# ST-LINK.net
KiCad netlist of a schematic drawn in Altium Designer
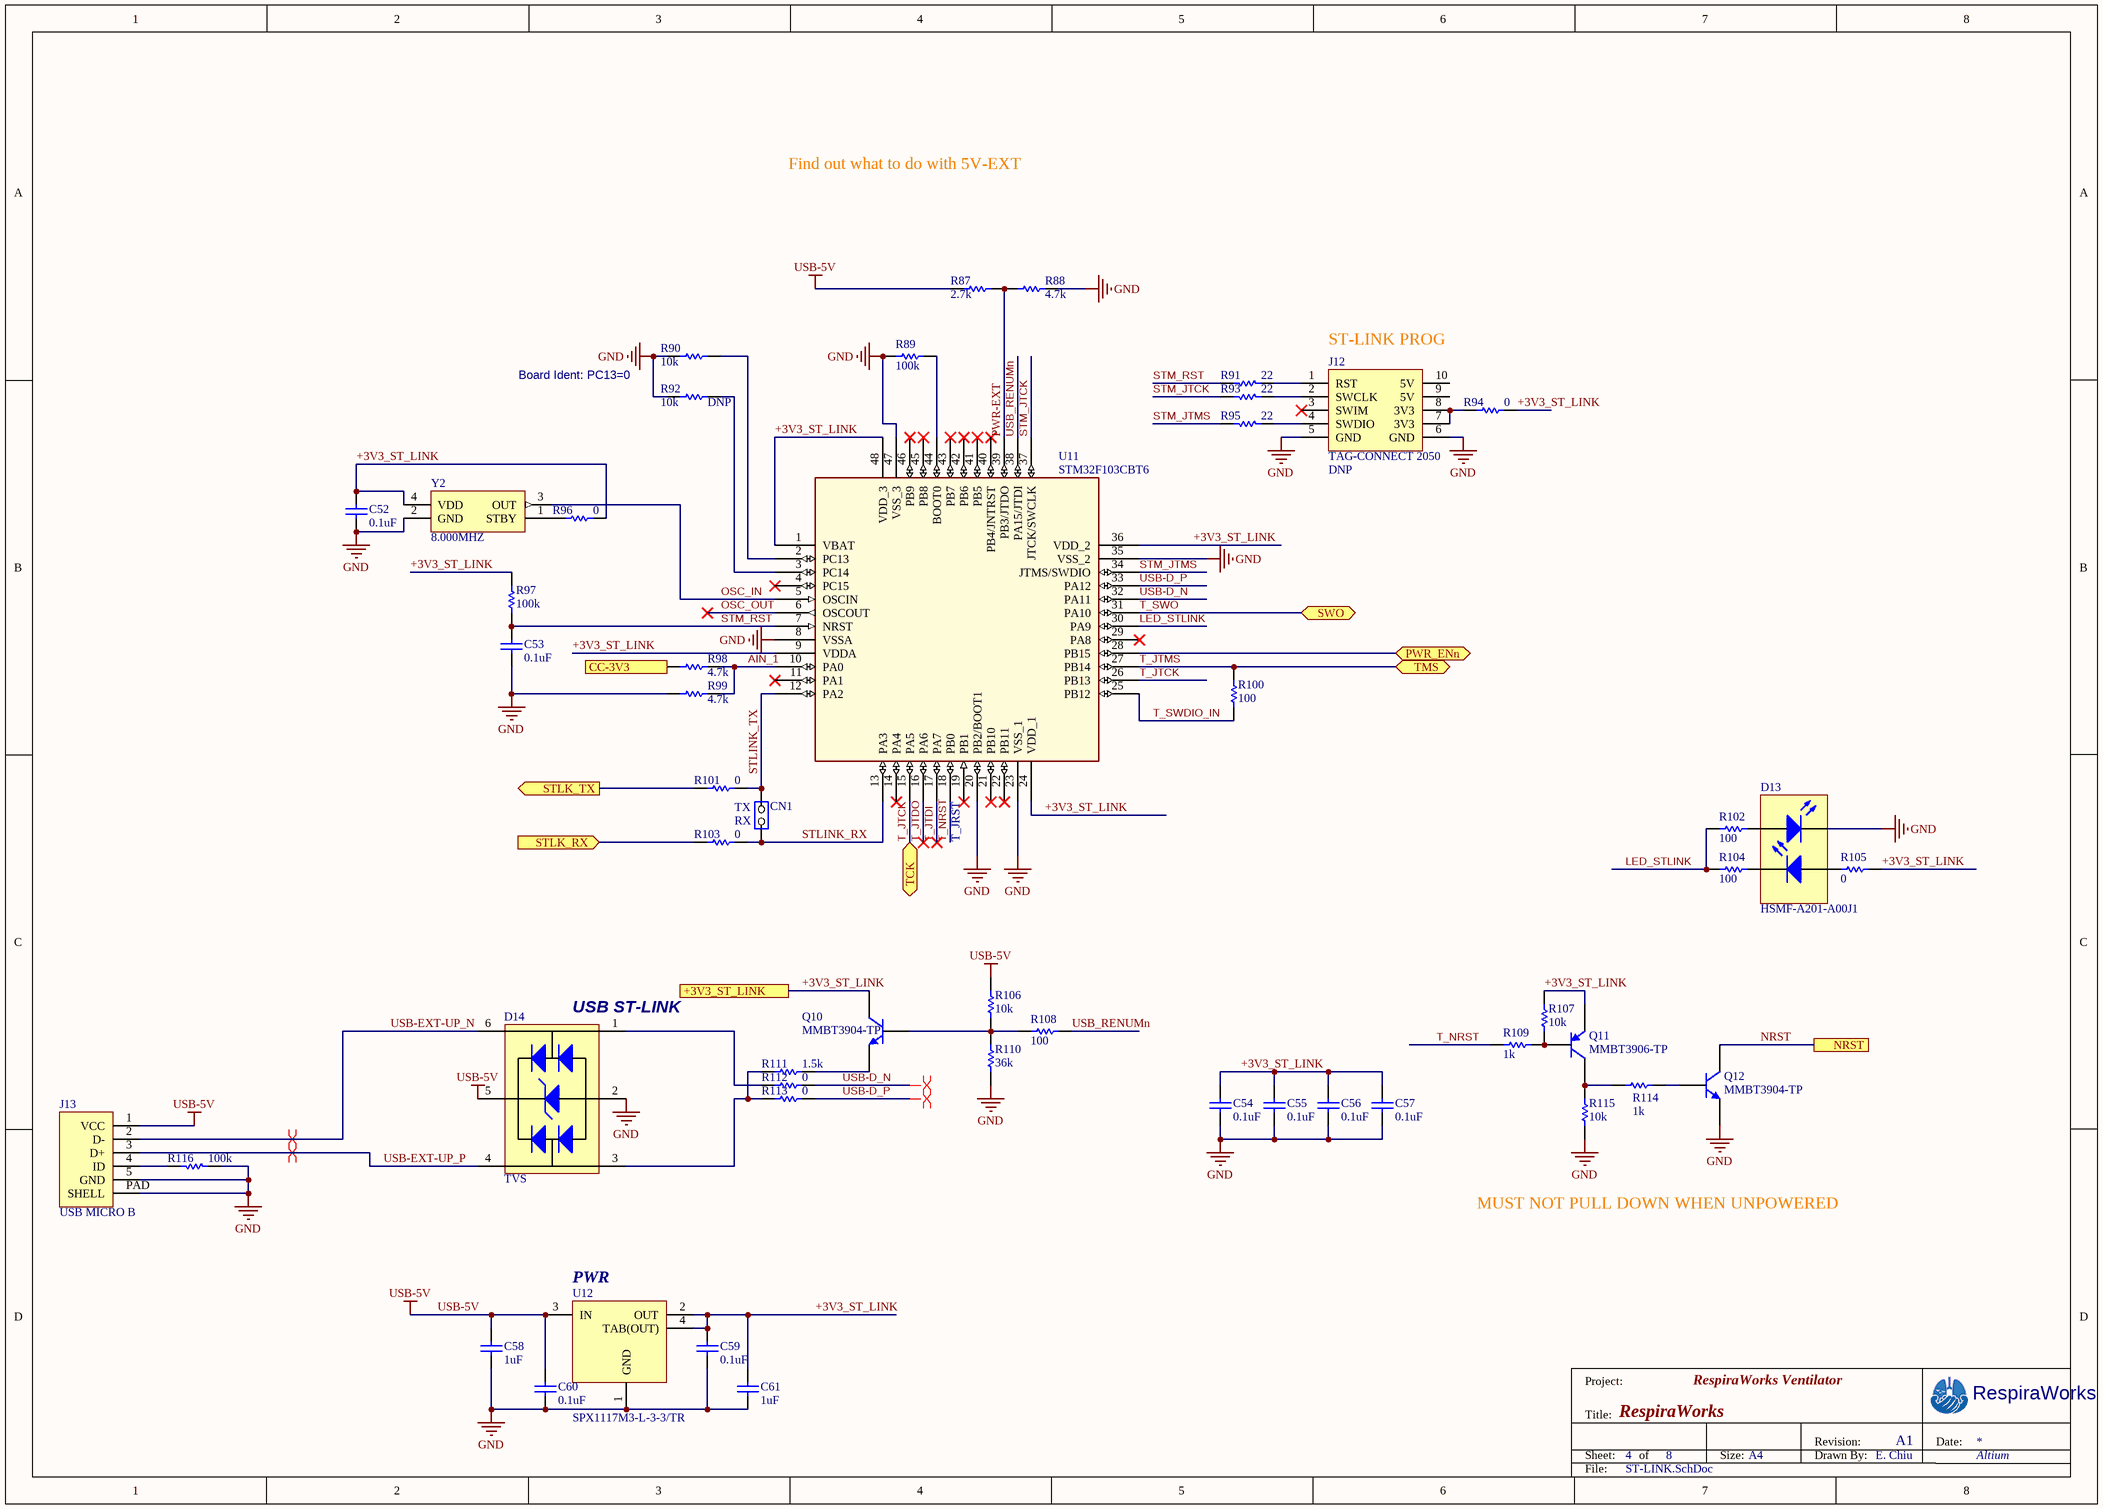
[diagram p0: ST-LINK.SchDoc]

(export (version "E")
  (design (tool "Eeschema 10.0.6"))
  (components
    (comp (ref "C52")
      (value "0.1uF")
      (footprint "CAP0603")
      (description "Cap 0603")
      (fields (field (name "MANUFACTURER") "Yageo") (field (name "VOLTAGE") "25V"))
      (libsource (lib "generic") (part "CAP 0603"))
    )
    (comp (ref "C53")
      (value "0.1uF")
      (footprint "CAP0603")
      (description "Cap 0603")
      (fields (field (name "MANUFACTURER") "Yageo") (field (name "VOLTAGE") "25V"))
      (libsource (lib "generic") (part "CAP 0603"))
    )
    (comp (ref "C54")
      (value "0.1uF")
      (footprint "CAP0603")
      (description "Cap 0603")
      (fields (field (name "MANUFACTURER") "Yageo") (field (name "VOLTAGE") "25V"))
      (libsource (lib "generic") (part "CAP 0603"))
    )
    (comp (ref "C55")
      (value "0.1uF")
      (footprint "CAP0603")
      (description "Cap 0603")
      (fields (field (name "MANUFACTURER") "Yageo") (field (name "VOLTAGE") "25V"))
      (libsource (lib "generic") (part "CAP 0603"))
    )
    (comp (ref "C56")
      (value "0.1uF")
      (footprint "CAP0603")
      (description "Cap 0603")
      (fields (field (name "MANUFACTURER") "Yageo") (field (name "VOLTAGE") "25V"))
      (libsource (lib "generic") (part "CAP 0603"))
    )
    (comp (ref "C57")
      (value "0.1uF")
      (footprint "CAP0603")
      (description "Cap 0603")
      (fields (field (name "MANUFACTURER") "Yageo") (field (name "VOLTAGE") "25V"))
      (libsource (lib "generic") (part "CAP 0603"))
    )
    (comp (ref "C58")
      (value "1uF")
      (footprint "CAP0603")
      (description "Cap 0603")
      (fields (field (name "MANUFACTURER") "TDK") (field (name "VOLTAGE") "25V"))
      (libsource (lib "generic") (part "CAP 0603"))
    )
    (comp (ref "C59")
      (value "0.1uF")
      (footprint "CAP0603")
      (description "Cap 0603")
      (fields (field (name "MANUFACTURER") "Yageo") (field (name "VOLTAGE") "25V"))
      (libsource (lib "generic") (part "CAP 0603"))
    )
    (comp (ref "C60")
      (value "0.1uF")
      (footprint "CAP0603")
      (description "Cap 0603")
      (fields (field (name "MANUFACTURER") "Yageo") (field (name "VOLTAGE") "25V"))
      (libsource (lib "generic") (part "CAP 0603"))
    )
    (comp (ref "C61")
      (value "1uF")
      (footprint "CAP0603")
      (description "Cap 0603")
      (fields (field (name "MANUFACTURER") "TDK") (field (name "VOLTAGE") "25V"))
      (libsource (lib "generic") (part "CAP 0603"))
    )
    (comp (ref "CN1")
      (value "~")
      (footprint "HDR1X2")
      (description "HEADER 2")
      (fields (field (name "MANUFACTURER") "Wurth"))
      (libsource (lib "MCD_TOOLS") (part "JP2"))
    )
    (comp (ref "D13")
      (value "*")
      (footprint "4-LED3228")
      (description "LED 3528 4PIN")
      (fields (field (name "MANUFACTURER P/N") "HSMF-A201-A00J1") (field (name "MANUFACTURER") "Broadcom"))
      (libsource (lib "generic") (part "LED 3228 4PIN"))
    )
    (comp (ref "D14")
      (value "TVS")
      (footprint "6-SOT23")
      (description "TVS, USB2.0, 15kV")
      (fields (field (name "MANUFACTURER") "ST Micro"))
      (libsource (lib "st") (part "USBLC6-2SC6"))
    )
    (comp (ref "J12")
      (value "TAG-CONNECT 2050")
      (footprint "TAG-CONNECT-2050")
      (description "10-pin TAG-CONNECT Bed of Nails footprint")
      (fields (field (name "DO NOT POPULATE") "DNP"))
      (libsource (lib "special") (part "TC-2050-STLINK"))
    )
    (comp (ref "J13")
      (value "USB MICRO B")
      (footprint "10118192-0001LF")
      (description "SMT USB MICRO B RECEPTACLE")
      (fields (field (name "MANUFACTURER") "Amphenol"))
      (libsource (lib "amphenol") (part "10118192-0001LF"))
    )
    (comp (ref "Q10")
      (value "MMBT3904")
      (footprint "3-SOT23")
      (description "Transistor, BJT NPN, General Purpose 40V")
      (fields
        (field (name "MANUFACTURER") "Micro Commercial")
        (field (name "MANUFACTURER P/N") "MMBT3904-TP")
      )
      (libsource (lib "fairchild") (part "MMBT3904"))
    )
    (comp (ref "Q11")
      (value "MMBT3906")
      (footprint "3-SOT23")
      (description "Transistor, BJT PNP, General Purpose 40V")
      (fields
        (field (name "MANUFACTURER") "Micro Commercial")
        (field (name "MANUFACTURER P/N") "MMBT3906-TP")
      )
      (libsource (lib "fairchild") (part "MMBT3906"))
    )
    (comp (ref "Q12")
      (value "MMBT3904")
      (footprint "3-SOT23")
      (description "Transistor, BJT NPN, General Purpose 40V")
      (fields
        (field (name "MANUFACTURER") "Micro Commercial")
        (field (name "MANUFACTURER P/N") "MMBT3904-TP")
      )
      (libsource (lib "fairchild") (part "MMBT3904"))
    )
    (comp (ref "R87")
      (value "2.7k")
      (footprint "RES0603")
      (description "Res 0603")
      (fields (field (name "MANUFACTURER") "Panasonic") (field (name "TOLERANCE") "1%"))
      (libsource (lib "generic") (part "RES 0603"))
    )
    (comp (ref "R88")
      (value "4.7k")
      (footprint "RES0603")
      (description "Res 0603")
      (fields (field (name "MANUFACTURER") "Yageo") (field (name "TOLERANCE") "1%"))
      (libsource (lib "generic") (part "RES 0603"))
    )
    (comp (ref "R89")
      (value "100k")
      (footprint "RES0603")
      (description "Res 0603")
      (fields (field (name "MANUFACTURER") "Panasonic") (field (name "TOLERANCE") "1%"))
      (libsource (lib "generic") (part "RES 0603"))
    )
    (comp (ref "R90")
      (value "10k")
      (footprint "RES0603")
      (description "Res 0603")
      (fields (field (name "MANUFACTURER") "Panasonic") (field (name "Comment") "RES 0603"))
      (libsource (lib "generic") (part "RES 0603"))
    )
    (comp (ref "R91")
      (value "22")
      (footprint "RES0603")
      (description "Res 0603")
      (fields (field (name "MANUFACTURER") "Yageo") (field (name "TOLERANCE") "1%"))
      (libsource (lib "generic") (part "RES 0603"))
    )
    (comp (ref "R92")
      (value "10k")
      (footprint "RES0603")
      (description "Res 0603")
      (fields
        (field (name "MANUFACTURER") "Panasonic")
        (field (name "DO NOT POPULATE") "DNP")
        (field (name "Comment") "RES 0603")
      )
      (libsource (lib "generic") (part "RES 0603"))
    )
    (comp (ref "R93")
      (value "22")
      (footprint "RES0603")
      (description "Res 0603")
      (fields (field (name "MANUFACTURER") "Yageo") (field (name "TOLERANCE") "1%"))
      (libsource (lib "generic") (part "RES 0603"))
    )
    (comp (ref "R94")
      (value "0")
      (footprint "RES0603")
      (description "Res 0603")
      (fields (field (name "MANUFACTURER") "Panasonic") (field (name "Comment") "RES 0603"))
      (libsource (lib "generic") (part "RES 0603"))
    )
    (comp (ref "R95")
      (value "22")
      (footprint "RES0603")
      (description "Res 0603")
      (fields (field (name "MANUFACTURER") "Yageo") (field (name "TOLERANCE") "1%"))
      (libsource (lib "generic") (part "RES 0603"))
    )
    (comp (ref "R96")
      (value "0")
      (footprint "RES0603")
      (description "Res 0603")
      (fields (field (name "MANUFACTURER") "Panasonic") (field (name "Comment") "RES 0603"))
      (libsource (lib "generic") (part "RES 0603"))
    )
    (comp (ref "R97")
      (value "100k")
      (footprint "RES0603")
      (description "Res 0603")
      (fields (field (name "MANUFACTURER") "Panasonic") (field (name "TOLERANCE") "1%"))
      (libsource (lib "generic") (part "RES 0603"))
    )
    (comp (ref "R98")
      (value "4.7k")
      (footprint "RES0603")
      (description "Res 0603")
      (fields (field (name "MANUFACTURER") "Yageo") (field (name "TOLERANCE") "1%"))
      (libsource (lib "generic") (part "RES 0603"))
    )
    (comp (ref "R99")
      (value "4.7k")
      (footprint "RES0603")
      (description "Res 0603")
      (fields (field (name "MANUFACTURER") "Yageo") (field (name "TOLERANCE") "1%"))
      (libsource (lib "generic") (part "RES 0603"))
    )
    (comp (ref "R100")
      (value "100")
      (footprint "RES0603")
      (description "Res 0603")
      (fields (field (name "MANUFACTURER") "Yageo") (field (name "TOLERANCE") "1%"))
      (libsource (lib "generic") (part "RES 0603"))
    )
    (comp (ref "R101")
      (value "0")
      (footprint "RES0603")
      (description "Res 0603")
      (fields (field (name "MANUFACTURER") "Panasonic") (field (name "Comment") "RES 0603"))
      (libsource (lib "generic") (part "RES 0603"))
    )
    (comp (ref "R102")
      (value "100")
      (footprint "RES0603")
      (description "Res 0603")
      (fields (field (name "MANUFACTURER") "Yageo") (field (name "TOLERANCE") "1%"))
      (libsource (lib "generic") (part "RES 0603"))
    )
    (comp (ref "R103")
      (value "0")
      (footprint "RES0603")
      (description "Res 0603")
      (fields (field (name "MANUFACTURER") "Panasonic") (field (name "Comment") "RES 0603"))
      (libsource (lib "generic") (part "RES 0603"))
    )
    (comp (ref "R104")
      (value "100")
      (footprint "RES0603")
      (description "Res 0603")
      (fields (field (name "MANUFACTURER") "Yageo") (field (name "TOLERANCE") "1%"))
      (libsource (lib "generic") (part "RES 0603"))
    )
    (comp (ref "R105")
      (value "0")
      (footprint "RES0603")
      (description "Res 0603")
      (fields (field (name "MANUFACTURER") "Panasonic") (field (name "Comment") "RES 0603"))
      (libsource (lib "generic") (part "RES 0603"))
    )
    (comp (ref "R106")
      (value "10k")
      (footprint "RES0603")
      (description "Res 0603")
      (fields (field (name "MANUFACTURER") "Panasonic") (field (name "Comment") "RES 0603"))
      (libsource (lib "generic") (part "RES 0603"))
    )
    (comp (ref "R107")
      (value "10k")
      (footprint "RES0603")
      (description "Res 0603")
      (fields (field (name "MANUFACTURER") "Panasonic") (field (name "Comment") "RES 0603"))
      (libsource (lib "generic") (part "RES 0603"))
    )
    (comp (ref "R108")
      (value "100")
      (footprint "RES0603")
      (description "Res 0603")
      (fields (field (name "MANUFACTURER") "Yageo") (field (name "TOLERANCE") "1%"))
      (libsource (lib "generic") (part "RES 0603"))
    )
    (comp (ref "R109")
      (value "1k")
      (footprint "RES0603")
      (description "Res 0603")
      (fields (field (name "MANUFACTURER") "Yageo") (field (name "TOLERANCE") "1%"))
      (libsource (lib "generic") (part "RES 0603"))
    )
    (comp (ref "R110")
      (value "36k")
      (footprint "RES0603")
      (description "Res 0603")
      (fields (field (name "MANUFACTURER") "Yageo") (field (name "TOLERANCE") "1%"))
      (libsource (lib "generic") (part "RES 0603"))
    )
    (comp (ref "R111")
      (value "1.5k")
      (footprint "RES0603")
      (description "Res 0603")
      (fields (field (name "MANUFACTURER") "Yageo") (field (name "TOLERANCE") "1%"))
      (libsource (lib "generic") (part "RES 0603"))
    )
    (comp (ref "R112")
      (value "0")
      (footprint "RES0603")
      (description "Res 0603")
      (fields (field (name "MANUFACTURER") "Panasonic") (field (name "Comment") "RES 0603"))
      (libsource (lib "generic") (part "RES 0603"))
    )
    (comp (ref "R113")
      (value "0")
      (footprint "RES0603")
      (description "Res 0603")
      (fields (field (name "MANUFACTURER") "Panasonic") (field (name "Comment") "RES 0603"))
      (libsource (lib "generic") (part "RES 0603"))
    )
    (comp (ref "R114")
      (value "1k")
      (footprint "RES0603")
      (description "Res 0603")
      (fields (field (name "MANUFACTURER") "Yageo") (field (name "TOLERANCE") "1%"))
      (libsource (lib "generic") (part "RES 0603"))
    )
    (comp (ref "R115")
      (value "10k")
      (footprint "RES0603")
      (description "Res 0603")
      (fields (field (name "MANUFACTURER") "Panasonic") (field (name "Comment") "RES 0603"))
      (libsource (lib "generic") (part "RES 0603"))
    )
    (comp (ref "R116")
      (value "100k")
      (footprint "RES0603")
      (description "Res 0603")
      (fields (field (name "MANUFACTURER") "Panasonic") (field (name "TOLERANCE") "1%"))
      (libsource (lib "generic") (part "RES 0603"))
    )
    (comp (ref "U11")
      (value "STM32F103CBT6")
      (footprint "48-LQFP")
      (description "Medium-density performance line ARM-based 32-bit MCU with 64KB Flash")
      (fields (field (name "MANUFACTURER") "ST Micro"))
      (libsource (lib "Nucleo_64") (part "STM32F103CBT6"))
    )
    (comp (ref "U12")
      (value "NCP1117ST33T3G")
      (footprint "3-SOT223")
      (description "LDO, 3.3V out, 1A, 20V in, SOT-223, 0.8W Pd max")
      (fields (field (name "MANUFACTURER") "Exar") (field (name "MANUFACTURER P/N") "SPX1117M3-L-3-3/TR"))
      (libsource (lib "on-semi") (part "NCP1117ST33T3G"))
    )
    (comp (ref "Y2")
      (value "8.000MHZ")
      (footprint "4-OSC3225")
      (description "OSC MEMS 8.000MHZ CMOS SMD")
      (fields (field (name "MANUFACTURER") "Abracon") (field (name "TOLERANCE") "50ppm"))
      (libsource (lib "abracon") (part "ASEMB-8.000MHZ-LC-T"))
    )
  )
  (nets
    (net (code "1") (name "/+3V3_ST_LINK") (class "Default")
      (node (ref "C52") (pin "2") (pinfunction "2_2") (pintype "passive"))
      (node (ref "C54") (pin "2") (pinfunction "2_2") (pintype "passive"))
      (node (ref "C55") (pin "2") (pinfunction "2_2") (pintype "passive"))
      (node (ref "C56") (pin "2") (pinfunction "2_2") (pintype "passive"))
      (node (ref "C57") (pin "2") (pinfunction "2_2") (pintype "passive"))
      (node (ref "C59") (pin "2") (pinfunction "2_2") (pintype "passive"))
      (node (ref "C61") (pin "2") (pinfunction "2_2") (pintype "passive"))
      (node (ref "Q10") (pin "3") (pinfunction "C_3") (pintype "passive"))
      (node (ref "Q11") (pin "2") (pinfunction "E_2") (pintype "passive"))
      (node (ref "R105") (pin "2") (pinfunction "2_2") (pintype "passive"))
      (node (ref "R107") (pin "1") (pinfunction "1_1") (pintype "passive"))
      (node (ref "R94") (pin "2") (pinfunction "2_2") (pintype "passive"))
      (node (ref "R96") (pin "1") (pinfunction "1_1") (pintype "passive"))
      (node (ref "R97") (pin "2") (pinfunction "2_2") (pintype "passive"))
      (node (ref "U11") (pin "1") (pinfunction "VBAT_1") (pintype "power_in"))
      (node (ref "U11") (pin "24") (pinfunction "VDD_1_24") (pintype "power_in"))
      (node (ref "U11") (pin "36") (pinfunction "VDD_2_36") (pintype "power_in"))
      (node (ref "U11") (pin "48") (pinfunction "VDD_3_48") (pintype "power_in"))
      (node (ref "U11") (pin "9") (pinfunction "VDDA_9") (pintype "power_in"))
      (node (ref "U12") (pin "2") (pinfunction "OUT_2") (pintype "passive"))
      (node (ref "U12") (pin "4") (pinfunction "TAB(OUT)_4") (pintype "passive"))
      (node (ref "Y2") (pin "4") (pinfunction "VDD_4") (pintype "passive"))
    )
    (net (code "2") (name "/AIN_1") (class "Default")
      (node (ref "R98") (pin "2") (pinfunction "2_2") (pintype "passive"))
      (node (ref "R99") (pin "2") (pinfunction "2_2") (pintype "passive"))
      (node (ref "U11") (pin "10") (pinfunction "PA0_10") (pintype "bidirectional"))
    )
    (net (code "3") (name "/CC-3V3") (class "Default")
      (node (ref "R98") (pin "1") (pinfunction "1_1") (pintype "passive"))
    )
    (net (code "4") (name "/LED_STLINK") (class "Default")
      (node (ref "R102") (pin "1") (pinfunction "1_1") (pintype "passive"))
      (node (ref "R104") (pin "1") (pinfunction "1_1") (pintype "passive"))
      (node (ref "U11") (pin "30") (pinfunction "PA9_30") (pintype "bidirectional"))
    )
    (net (code "5") (name "/NRST") (class "Default")
      (node (ref "Q12") (pin "3") (pinfunction "C_3") (pintype "passive"))
    )
    (net (code "6") (name "/OSC_IN") (class "Default")
      (node (ref "U11") (pin "5") (pinfunction "OSCIN_5") (pintype "input"))
      (node (ref "Y2") (pin "3") (pinfunction "OUT_3") (pintype "output"))
    )
    (net (code "7") (name "/OSC_OUT") (class "Default")
      (node (ref "U11") (pin "6") (pinfunction "OSCOUT_6") (pintype "output+no_connect"))
    )
    (net (code "8") (name "/PWR-EXT") (class "Default")
      (node (ref "R87") (pin "2") (pinfunction "2_2") (pintype "passive"))
      (node (ref "R88") (pin "1") (pinfunction "1_1") (pintype "passive"))
      (node (ref "U11") (pin "39") (pinfunction "PB3/JTDO_39") (pintype "bidirectional"))
    )
    (net (code "9") (name "/PWR_ENn") (class "Default")
      (node (ref "U11") (pin "28") (pinfunction "PB15_28") (pintype "bidirectional"))
    )
    (net (code "10") (name "/STLINK_RX") (class "Default")
      (node (ref "CN1") (pin "1") (pinfunction "COMMON_1") (pintype "passive"))
      (node (ref "R103") (pin "2") (pinfunction "2_2") (pintype "passive"))
      (node (ref "U11") (pin "13") (pinfunction "PA3_13") (pintype "bidirectional"))
    )
    (net (code "11") (name "/STLINK_TX") (class "Default")
      (node (ref "CN1") (pin "2") (pinfunction "NO_2") (pintype "passive"))
      (node (ref "R101") (pin "2") (pinfunction "2_2") (pintype "passive"))
      (node (ref "U11") (pin "12") (pinfunction "PA2_12") (pintype "bidirectional"))
    )
    (net (code "12") (name "/STLK_RX") (class "Default")
      (node (ref "R103") (pin "1") (pinfunction "1_1") (pintype "passive"))
    )
    (net (code "13") (name "/STLK_TX") (class "Default")
      (node (ref "R101") (pin "1") (pinfunction "1_1") (pintype "passive"))
    )
    (net (code "14") (name "/STM_JTCK") (class "Default")
      (node (ref "R93") (pin "2") (pinfunction "2_2") (pintype "passive"))
      (node (ref "U11") (pin "37") (pinfunction "JTCK/SWCLK_37") (pintype "bidirectional"))
    )
    (net (code "15") (name "/STM_JTMS") (class "Default")
      (node (ref "R95") (pin "2") (pinfunction "2_2") (pintype "passive"))
      (node (ref "U11") (pin "34") (pinfunction "JTMS/SWDIO_34") (pintype "bidirectional"))
    )
    (net (code "16") (name "/STM_RST") (class "Default")
      (node (ref "C53") (pin "2") (pinfunction "2_2") (pintype "passive"))
      (node (ref "R91") (pin "2") (pinfunction "2_2") (pintype "passive"))
      (node (ref "R97") (pin "1") (pinfunction "1_1") (pintype "passive"))
      (node (ref "U11") (pin "7") (pinfunction "NRST_7") (pintype "input"))
    )
    (net (code "17") (name "/T_JTCK") (class "Default")
      (node (ref "U11") (pin "15") (pinfunction "PA5_15") (pintype "bidirectional"))
      (node (ref "U11") (pin "26") (pinfunction "PB13_26") (pintype "bidirectional"))
    )
    (net (code "18") (name "/T_JTDI") (class "Default")
      (node (ref "U11") (pin "17") (pinfunction "PA7_17") (pintype "bidirectional+no_connect"))
    )
    (net (code "19") (name "/T_JTDO") (class "Default")
      (node (ref "U11") (pin "16") (pinfunction "PA6_16") (pintype "bidirectional+no_connect"))
    )
    (net (code "20") (name "/T_JTMS") (class "Default")
      (node (ref "R100") (pin "2") (pinfunction "2_2") (pintype "passive"))
      (node (ref "U11") (pin "27") (pinfunction "PB14_27") (pintype "bidirectional"))
    )
    (net (code "21") (name "/T_NRST") (class "Default")
      (node (ref "R109") (pin "2") (pinfunction "2_2") (pintype "passive"))
      (node (ref "U11") (pin "18") (pinfunction "PB0_18") (pintype "bidirectional"))
    )
    (net (code "22") (name "/T_SWDIO_IN") (class "Default")
      (node (ref "R100") (pin "1") (pinfunction "1_1") (pintype "passive"))
      (node (ref "U11") (pin "25") (pinfunction "PB12_25") (pintype "bidirectional"))
    )
    (net (code "23") (name "/T_SWO") (class "Default")
      (node (ref "U11") (pin "31") (pinfunction "PA10_31") (pintype "bidirectional"))
    )
    (net (code "24") (name "/USB-D_N") (class "Default")
      (node (ref "R112") (pin "2") (pinfunction "2_2") (pintype "passive"))
      (node (ref "U11") (pin "32") (pinfunction "PA11_32") (pintype "bidirectional"))
    )
    (net (code "25") (name "/USB-D_P") (class "Default")
      (node (ref "R113") (pin "2") (pinfunction "2_2") (pintype "passive"))
      (node (ref "U11") (pin "33") (pinfunction "PA12_33") (pintype "bidirectional"))
    )
    (net (code "26") (name "/USB-EXT-UP_N") (class "Default")
      (node (ref "D14") (pin "6") (pinfunction "IO1_6") (pintype "passive"))
      (node (ref "J13") (pin "2") (pinfunction "D-_2") (pintype "passive"))
    )
    (net (code "27") (name "/USB-EXT-UP_P") (class "Default")
      (node (ref "D14") (pin "4") (pinfunction "IO3_4") (pintype "passive"))
      (node (ref "J13") (pin "3") (pinfunction "D+_3") (pintype "passive"))
    )
    (net (code "28") (name "/USB_RENUMn") (class "Default")
      (node (ref "R108") (pin "1") (pinfunction "1_1") (pintype "passive"))
      (node (ref "U11") (pin "38") (pinfunction "PA15/JTDI_38") (pintype "bidirectional"))
    )
    (net (code "29") (name "GND") (class "Default")
      (node (ref "C52") (pin "1") (pinfunction "1_1") (pintype "passive"))
      (node (ref "C53") (pin "1") (pinfunction "1_1") (pintype "passive"))
      (node (ref "C54") (pin "1") (pinfunction "1_1") (pintype "passive"))
      (node (ref "C55") (pin "1") (pinfunction "1_1") (pintype "passive"))
      (node (ref "C56") (pin "1") (pinfunction "1_1") (pintype "passive"))
      (node (ref "C57") (pin "1") (pinfunction "1_1") (pintype "passive"))
      (node (ref "C58") (pin "1") (pinfunction "1_1") (pintype "passive"))
      (node (ref "C59") (pin "1") (pinfunction "1_1") (pintype "passive"))
      (node (ref "C60") (pin "1") (pinfunction "1_1") (pintype "passive"))
      (node (ref "C61") (pin "1") (pinfunction "1_1") (pintype "passive"))
      (node (ref "D13") (pin "1") (pinfunction "K1_1") (pintype "passive"))
      (node (ref "D14") (pin "2") (pinfunction "GND_2") (pintype "passive"))
      (node (ref "J12") (pin "5") (pinfunction "GND_5") (pintype "passive"))
      (node (ref "J12") (pin "6") (pinfunction "GND_6") (pintype "passive"))
      (node (ref "J13") (pin "5") (pinfunction "GND_5") (pintype "passive"))
      (node (ref "J13") (pin "PAD") (pinfunction "SHELL_PAD") (pintype "passive"))
      (node (ref "Q12") (pin "2") (pinfunction "E_2") (pintype "passive"))
      (node (ref "R110") (pin "1") (pinfunction "1_1") (pintype "passive"))
      (node (ref "R115") (pin "2") (pinfunction "2_2") (pintype "passive"))
      (node (ref "R116") (pin "1") (pinfunction "1_1") (pintype "passive"))
      (node (ref "R88") (pin "2") (pinfunction "2_2") (pintype "passive"))
      (node (ref "R89") (pin "2") (pinfunction "2_2") (pintype "passive"))
      (node (ref "R90") (pin "2") (pinfunction "2_2") (pintype "passive"))
      (node (ref "R92") (pin "2") (pinfunction "2_2") (pintype "passive"))
      (node (ref "R99") (pin "1") (pinfunction "1_1") (pintype "passive"))
      (node (ref "U11") (pin "20") (pinfunction "PB2/BOOT1_20") (pintype "bidirectional"))
      (node (ref "U11") (pin "23") (pinfunction "VSS_1_23") (pintype "power_in"))
      (node (ref "U11") (pin "35") (pinfunction "VSS_2_35") (pintype "power_in"))
      (node (ref "U11") (pin "47") (pinfunction "VSS_3_47") (pintype "power_in"))
      (node (ref "U11") (pin "8") (pinfunction "VSSA_8") (pintype "power_in"))
      (node (ref "U12") (pin "1") (pinfunction "GND_1") (pintype "passive"))
      (node (ref "Y2") (pin "2") (pinfunction "GND_2") (pintype "passive"))
    )
    (net (code "30") (name "Net-(D13-A1)") (class "Default")
      (node (ref "D13") (pin "2") (pinfunction "A1_2") (pintype "passive"))
      (node (ref "R102") (pin "2") (pinfunction "2_2") (pintype "passive"))
    )
    (net (code "31") (name "Net-(D13-A2)") (class "Default")
      (node (ref "D13") (pin "4") (pinfunction "A2_4") (pintype "passive"))
      (node (ref "R105") (pin "1") (pinfunction "1_1") (pintype "passive"))
    )
    (net (code "32") (name "Net-(D13-K2)") (class "Default")
      (node (ref "D13") (pin "3") (pinfunction "K2_3") (pintype "passive"))
      (node (ref "R104") (pin "2") (pinfunction "2_2") (pintype "passive"))
    )
    (net (code "33") (name "Net-(D14-IO1-Pad1)") (class "Default")
      (node (ref "D14") (pin "1") (pinfunction "IO1_1") (pintype "passive"))
      (node (ref "R112") (pin "1") (pinfunction "1_1") (pintype "passive"))
    )
    (net (code "34") (name "Net-(D14-IO2)") (class "Default")
      (node (ref "D14") (pin "3") (pinfunction "IO2_3") (pintype "passive"))
      (node (ref "R111") (pin "2") (pinfunction "2_2") (pintype "passive"))
      (node (ref "R113") (pin "1") (pinfunction "1_1") (pintype "passive"))
    )
    (net (code "35") (name "Net-(J12-3V3-Pad7)") (class "Default")
      (node (ref "J12") (pin "7") (pinfunction "3V3_7") (pintype "passive"))
      (node (ref "J12") (pin "8") (pinfunction "3V3_8") (pintype "passive"))
      (node (ref "R94") (pin "1") (pinfunction "1_1") (pintype "passive"))
    )
    (net (code "36") (name "Net-(J12-RST)") (class "Default")
      (node (ref "J12") (pin "1") (pinfunction "RST_1") (pintype "passive"))
      (node (ref "R91") (pin "1") (pinfunction "1_1") (pintype "passive"))
    )
    (net (code "37") (name "Net-(J12-SWCLK)") (class "Default")
      (node (ref "J12") (pin "2") (pinfunction "SWCLK_2") (pintype "passive"))
      (node (ref "R93") (pin "1") (pinfunction "1_1") (pintype "passive"))
    )
    (net (code "38") (name "Net-(J12-SWDIO)") (class "Default")
      (node (ref "J12") (pin "4") (pinfunction "SWDIO_4") (pintype "passive"))
      (node (ref "R95") (pin "1") (pinfunction "1_1") (pintype "passive"))
    )
    (net (code "39") (name "Net-(J13-ID)") (class "Default")
      (node (ref "J13") (pin "4") (pinfunction "ID_4") (pintype "passive"))
      (node (ref "R116") (pin "2") (pinfunction "2_2") (pintype "passive"))
    )
    (net (code "40") (name "Net-(Q10-B)") (class "Default")
      (node (ref "Q10") (pin "1") (pinfunction "B_1") (pintype "passive"))
      (node (ref "R106") (pin "1") (pinfunction "1_1") (pintype "passive"))
      (node (ref "R108") (pin "2") (pinfunction "2_2") (pintype "passive"))
      (node (ref "R110") (pin "2") (pinfunction "2_2") (pintype "passive"))
    )
    (net (code "41") (name "Net-(Q10-E)") (class "Default")
      (node (ref "Q10") (pin "2") (pinfunction "E_2") (pintype "passive"))
      (node (ref "R111") (pin "1") (pinfunction "1_1") (pintype "passive"))
    )
    (net (code "42") (name "Net-(Q11-B)") (class "Default")
      (node (ref "Q11") (pin "1") (pinfunction "B_1") (pintype "passive"))
      (node (ref "R107") (pin "2") (pinfunction "2_2") (pintype "passive"))
      (node (ref "R109") (pin "1") (pinfunction "1_1") (pintype "passive"))
    )
    (net (code "43") (name "Net-(Q11-C)") (class "Default")
      (node (ref "Q11") (pin "3") (pinfunction "C_3") (pintype "passive"))
      (node (ref "R114") (pin "2") (pinfunction "2_2") (pintype "passive"))
      (node (ref "R115") (pin "1") (pinfunction "1_1") (pintype "passive"))
    )
    (net (code "44") (name "Net-(Q12-B)") (class "Default")
      (node (ref "Q12") (pin "1") (pinfunction "B_1") (pintype "passive"))
      (node (ref "R114") (pin "1") (pinfunction "1_1") (pintype "passive"))
    )
    (net (code "45") (name "Net-(U11-BOOT0)") (class "Default")
      (node (ref "R89") (pin "1") (pinfunction "1_1") (pintype "passive"))
      (node (ref "U11") (pin "44") (pinfunction "BOOT0_44") (pintype "bidirectional"))
    )
    (net (code "46") (name "Net-(U11-PC13)") (class "Default")
      (node (ref "R90") (pin "1") (pinfunction "1_1") (pintype "passive"))
      (node (ref "U11") (pin "2") (pinfunction "PC13_2") (pintype "bidirectional"))
    )
    (net (code "47") (name "Net-(U11-PC14)") (class "Default")
      (node (ref "R92") (pin "1") (pinfunction "1_1") (pintype "passive"))
      (node (ref "U11") (pin "3") (pinfunction "PC14_3") (pintype "bidirectional"))
    )
    (net (code "48") (name "Net-(Y2-STBY)") (class "Default")
      (node (ref "R96") (pin "2") (pinfunction "2_2") (pintype "passive"))
      (node (ref "Y2") (pin "1") (pinfunction "STBY_1") (pintype "passive"))
    )
    (net (code "49") (name "USB-5V") (class "Default")
      (node (ref "C58") (pin "2") (pinfunction "2_2") (pintype "passive"))
      (node (ref "C60") (pin "2") (pinfunction "2_2") (pintype "passive"))
      (node (ref "D14") (pin "5") (pinfunction "VBUS_5") (pintype "passive"))
      (node (ref "J13") (pin "1") (pinfunction "VCC_1") (pintype "passive"))
      (node (ref "R106") (pin "2") (pinfunction "2_2") (pintype "passive"))
      (node (ref "R87") (pin "1") (pinfunction "1_1") (pintype "passive"))
      (node (ref "U12") (pin "3") (pinfunction "IN_3") (pintype "passive"))
    )
    (net (code "50") (name "unconnected-(J12-5V-Pad9)") (class "Default")
      (node (ref "J12") (pin "9") (pinfunction "5V_9") (pintype "passive"))
    )
    (net (code "51") (name "unconnected-(J12-5V-Pad10)") (class "Default")
      (node (ref "J12") (pin "10") (pinfunction "5V_10") (pintype "passive"))
    )
    (net (code "52") (name "unconnected-(J12-SWIM-Pad3)") (class "Default")
      (node (ref "J12") (pin "3") (pinfunction "SWIM_3") (pintype "passive+no_connect"))
    )
    (net (code "53") (name "unconnected-(U11-PA1-Pad11)") (class "Default")
      (node (ref "U11") (pin "11") (pinfunction "PA1_11") (pintype "bidirectional+no_connect"))
    )
    (net (code "54") (name "unconnected-(U11-PA4-Pad14)") (class "Default")
      (node (ref "U11") (pin "14") (pinfunction "PA4_14") (pintype "bidirectional+no_connect"))
    )
    (net (code "55") (name "unconnected-(U11-PA8-Pad29)") (class "Default")
      (node (ref "U11") (pin "29") (pinfunction "PA8_29") (pintype "bidirectional+no_connect"))
    )
    (net (code "56") (name "unconnected-(U11-PB1-Pad19)") (class "Default")
      (node (ref "U11") (pin "19") (pinfunction "PB1_19") (pintype "input+no_connect"))
    )
    (net (code "57") (name "unconnected-(U11-PB4{slash}JNTRST-Pad40)") (class "Default")
      (node (ref "U11") (pin "40") (pinfunction "PB4/JNTRST_40") (pintype "bidirectional+no_connect"))
    )
    (net (code "58") (name "unconnected-(U11-PB5-Pad41)") (class "Default")
      (node (ref "U11") (pin "41") (pinfunction "PB5_41") (pintype "bidirectional+no_connect"))
    )
    (net (code "59") (name "unconnected-(U11-PB6-Pad42)") (class "Default")
      (node (ref "U11") (pin "42") (pinfunction "PB6_42") (pintype "bidirectional+no_connect"))
    )
    (net (code "60") (name "unconnected-(U11-PB7-Pad43)") (class "Default")
      (node (ref "U11") (pin "43") (pinfunction "PB7_43") (pintype "bidirectional+no_connect"))
    )
    (net (code "61") (name "unconnected-(U11-PB8-Pad45)") (class "Default")
      (node (ref "U11") (pin "45") (pinfunction "PB8_45") (pintype "bidirectional+no_connect"))
    )
    (net (code "62") (name "unconnected-(U11-PB9-Pad46)") (class "Default")
      (node (ref "U11") (pin "46") (pinfunction "PB9_46") (pintype "bidirectional+no_connect"))
    )
    (net (code "63") (name "unconnected-(U11-PB10-Pad21)") (class "Default")
      (node (ref "U11") (pin "21") (pinfunction "PB10_21") (pintype "bidirectional+no_connect"))
    )
    (net (code "64") (name "unconnected-(U11-PB11-Pad22)") (class "Default")
      (node (ref "U11") (pin "22") (pinfunction "PB11_22") (pintype "bidirectional+no_connect"))
    )
    (net (code "65") (name "unconnected-(U11-PC15-Pad4)") (class "Default")
      (node (ref "U11") (pin "4") (pinfunction "PC15_4") (pintype "bidirectional+no_connect"))
    )
  )
)
